# powersupply.net
KiCad netlist of a schematic drawn in EAGLE
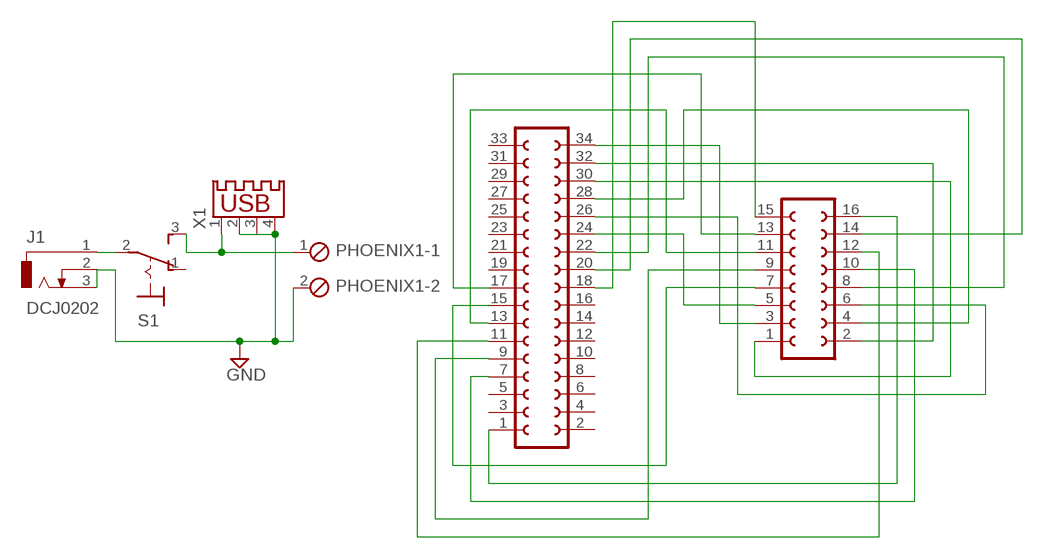
[diagram p0: schematic, sheet 1]

(export (version "E")
  (design (tool "Eeschema 10.0.6"))
  (components
    (comp (ref "J1")
      (value "DCJ0202")
      (footprint "eagle-import:DCJ0202")
      (libsource (lib "eagle-import") (part "DCJ0202"))
    )
    (comp (ref "PHOENIX1")
      (value "MPT2")
      (footprint "eagle-import:2POL254")
      (libsource (lib "eagle-import") (part "MPT2"))
    )
    (comp (ref "S1")
      (value "M9040P")
      (footprint "eagle-import:M9040P")
      (libsource (lib "eagle-import") (part "M9040P"))
    )
    (comp (ref "SV1")
      (value "FE17-2")
      (footprint "eagle-import:FE17-2")
      (libsource (lib "eagle-import") (part "FE17-2"))
    )
    (comp (ref "SV2")
      (value "FE08-2")
      (footprint "eagle-import:FE08-2")
      (libsource (lib "eagle-import") (part "FE08-2"))
    )
    (comp (ref "X1")
      (value "USB-A003")
      (footprint "eagle-import:USB-A003")
      (libsource (lib "eagle-import") (part "USB-A003"))
    )
  )
  (nets
    (net (code "1") (name "GND") (class "Default")
      (node (ref "J1") (pin "2") (pinfunction "2_2") (pintype "passive"))
      (node (ref "J1") (pin "3") (pinfunction "3_3") (pintype "passive"))
      (node (ref "PHOENIX1") (pin "2") (pinfunction "1_2") (pintype "passive"))
      (node (ref "X1") (pin "2") (pinfunction "2_2") (pintype "passive"))
      (node (ref "X1") (pin "3") (pinfunction "3_3") (pintype "passive"))
      (node (ref "X1") (pin "4") (pinfunction "4_4") (pintype "passive"))
    )
    (net (code "2") (name "Net-(S1-P)") (class "Default")
      (node (ref "J1") (pin "1") (pinfunction "1_1") (pintype "passive"))
      (node (ref "S1") (pin "2") (pinfunction "P_2") (pintype "passive"))
    )
    (net (code "3") (name "Net-(S1-S)") (class "Default")
      (node (ref "PHOENIX1") (pin "1") (pinfunction "1_1") (pintype "passive"))
      (node (ref "S1") (pin "3") (pinfunction "S_3") (pintype "passive"))
      (node (ref "X1") (pin "1") (pinfunction "1_1") (pintype "passive"))
    )
    (net (code "4") (name "Net-(SV1-Pad1)") (class "Default")
      (node (ref "SV1") (pin "1") (pinfunction "1_1") (pintype "passive"))
      (node (ref "SV2") (pin "16") (pinfunction "16_16") (pintype "passive"))
    )
    (net (code "5") (name "Net-(SV1-Pad7)") (class "Default")
      (node (ref "SV1") (pin "7") (pinfunction "7_7") (pintype "passive"))
      (node (ref "SV2") (pin "10") (pinfunction "10_10") (pintype "passive"))
    )
    (net (code "6") (name "Net-(SV1-Pad9)") (class "Default")
      (node (ref "SV1") (pin "9") (pinfunction "9_9") (pintype "passive"))
      (node (ref "SV2") (pin "9") (pinfunction "9_9") (pintype "passive"))
    )
    (net (code "7") (name "Net-(SV1-Pad11)") (class "Default")
      (node (ref "SV1") (pin "11") (pinfunction "11_11") (pintype "passive"))
      (node (ref "SV2") (pin "12") (pinfunction "12_12") (pintype "passive"))
    )
    (net (code "8") (name "Net-(SV1-Pad13)") (class "Default")
      (node (ref "SV1") (pin "13") (pinfunction "13_13") (pintype "passive"))
      (node (ref "SV2") (pin "11") (pinfunction "11_11") (pintype "passive"))
    )
    (net (code "9") (name "Net-(SV1-Pad15)") (class "Default")
      (node (ref "SV1") (pin "15") (pinfunction "15_15") (pintype "passive"))
      (node (ref "SV2") (pin "7") (pinfunction "7_7") (pintype "passive"))
    )
    (net (code "10") (name "Net-(SV1-Pad17)") (class "Default")
      (node (ref "SV1") (pin "17") (pinfunction "17_17") (pintype "passive"))
      (node (ref "SV2") (pin "13") (pinfunction "13_13") (pintype "passive"))
    )
    (net (code "11") (name "Net-(SV1-Pad18)") (class "Default")
      (node (ref "SV1") (pin "18") (pinfunction "18_18") (pintype "passive"))
      (node (ref "SV2") (pin "15") (pinfunction "15_15") (pintype "passive"))
    )
    (net (code "12") (name "Net-(SV1-Pad20)") (class "Default")
      (node (ref "SV1") (pin "20") (pinfunction "20_20") (pintype "passive"))
      (node (ref "SV2") (pin "14") (pinfunction "14_14") (pintype "passive"))
    )
    (net (code "13") (name "Net-(SV1-Pad22)") (class "Default")
      (node (ref "SV1") (pin "22") (pinfunction "22_22") (pintype "passive"))
      (node (ref "SV2") (pin "8") (pinfunction "8_8") (pintype "passive"))
    )
    (net (code "14") (name "Net-(SV1-Pad24)") (class "Default")
      (node (ref "SV1") (pin "24") (pinfunction "24_24") (pintype "passive"))
      (node (ref "SV2") (pin "5") (pinfunction "5_5") (pintype "passive"))
    )
    (net (code "15") (name "Net-(SV1-Pad26)") (class "Default")
      (node (ref "SV1") (pin "26") (pinfunction "26_26") (pintype "passive"))
      (node (ref "SV2") (pin "6") (pinfunction "6_6") (pintype "passive"))
    )
    (net (code "16") (name "Net-(SV1-Pad28)") (class "Default")
      (node (ref "SV1") (pin "28") (pinfunction "28_28") (pintype "passive"))
      (node (ref "SV2") (pin "4") (pinfunction "4_4") (pintype "passive"))
    )
    (net (code "17") (name "Net-(SV1-Pad30)") (class "Default")
      (node (ref "SV1") (pin "30") (pinfunction "30_30") (pintype "passive"))
      (node (ref "SV2") (pin "1") (pinfunction "1_1") (pintype "passive"))
    )
    (net (code "18") (name "Net-(SV1-Pad32)") (class "Default")
      (node (ref "SV1") (pin "32") (pinfunction "32_32") (pintype "passive"))
      (node (ref "SV2") (pin "2") (pinfunction "2_2") (pintype "passive"))
    )
    (net (code "19") (name "Net-(SV1-Pad34)") (class "Default")
      (node (ref "SV1") (pin "34") (pinfunction "34_34") (pintype "passive"))
      (node (ref "SV2") (pin "3") (pinfunction "3_3") (pintype "passive"))
    )
    (net (code "20") (name "unconnected-(S1-O-Pad1)") (class "Default")
      (node (ref "S1") (pin "1") (pinfunction "O_1") (pintype "passive"))
    )
    (net (code "21") (name "unconnected-(SV1-Pad2)") (class "Default")
      (node (ref "SV1") (pin "2") (pinfunction "2_2") (pintype "passive"))
    )
    (net (code "22") (name "unconnected-(SV1-Pad3)") (class "Default")
      (node (ref "SV1") (pin "3") (pinfunction "3_3") (pintype "passive"))
    )
    (net (code "23") (name "unconnected-(SV1-Pad4)") (class "Default")
      (node (ref "SV1") (pin "4") (pinfunction "4_4") (pintype "passive"))
    )
    (net (code "24") (name "unconnected-(SV1-Pad5)") (class "Default")
      (node (ref "SV1") (pin "5") (pinfunction "5_5") (pintype "passive"))
    )
    (net (code "25") (name "unconnected-(SV1-Pad6)") (class "Default")
      (node (ref "SV1") (pin "6") (pinfunction "6_6") (pintype "passive"))
    )
    (net (code "26") (name "unconnected-(SV1-Pad8)") (class "Default")
      (node (ref "SV1") (pin "8") (pinfunction "8_8") (pintype "passive"))
    )
    (net (code "27") (name "unconnected-(SV1-Pad10)") (class "Default")
      (node (ref "SV1") (pin "10") (pinfunction "10_10") (pintype "passive"))
    )
    (net (code "28") (name "unconnected-(SV1-Pad12)") (class "Default")
      (node (ref "SV1") (pin "12") (pinfunction "12_12") (pintype "passive"))
    )
    (net (code "29") (name "unconnected-(SV1-Pad14)") (class "Default")
      (node (ref "SV1") (pin "14") (pinfunction "14_14") (pintype "passive"))
    )
    (net (code "30") (name "unconnected-(SV1-Pad16)") (class "Default")
      (node (ref "SV1") (pin "16") (pinfunction "16_16") (pintype "passive"))
    )
    (net (code "31") (name "unconnected-(SV1-Pad19)") (class "Default")
      (node (ref "SV1") (pin "19") (pinfunction "19_19") (pintype "passive"))
    )
    (net (code "32") (name "unconnected-(SV1-Pad21)") (class "Default")
      (node (ref "SV1") (pin "21") (pinfunction "21_21") (pintype "passive"))
    )
    (net (code "33") (name "unconnected-(SV1-Pad23)") (class "Default")
      (node (ref "SV1") (pin "23") (pinfunction "23_23") (pintype "passive"))
    )
    (net (code "34") (name "unconnected-(SV1-Pad25)") (class "Default")
      (node (ref "SV1") (pin "25") (pinfunction "25_25") (pintype "passive"))
    )
    (net (code "35") (name "unconnected-(SV1-Pad27)") (class "Default")
      (node (ref "SV1") (pin "27") (pinfunction "27_27") (pintype "passive"))
    )
    (net (code "36") (name "unconnected-(SV1-Pad29)") (class "Default")
      (node (ref "SV1") (pin "29") (pinfunction "29_29") (pintype "passive"))
    )
    (net (code "37") (name "unconnected-(SV1-Pad31)") (class "Default")
      (node (ref "SV1") (pin "31") (pinfunction "31_31") (pintype "passive"))
    )
    (net (code "38") (name "unconnected-(SV1-Pad33)") (class "Default")
      (node (ref "SV1") (pin "33") (pinfunction "33_33") (pintype "passive"))
    )
  )
)
